# RTM_CON.net
KiCad netlist of a schematic drawn in Altium Designer
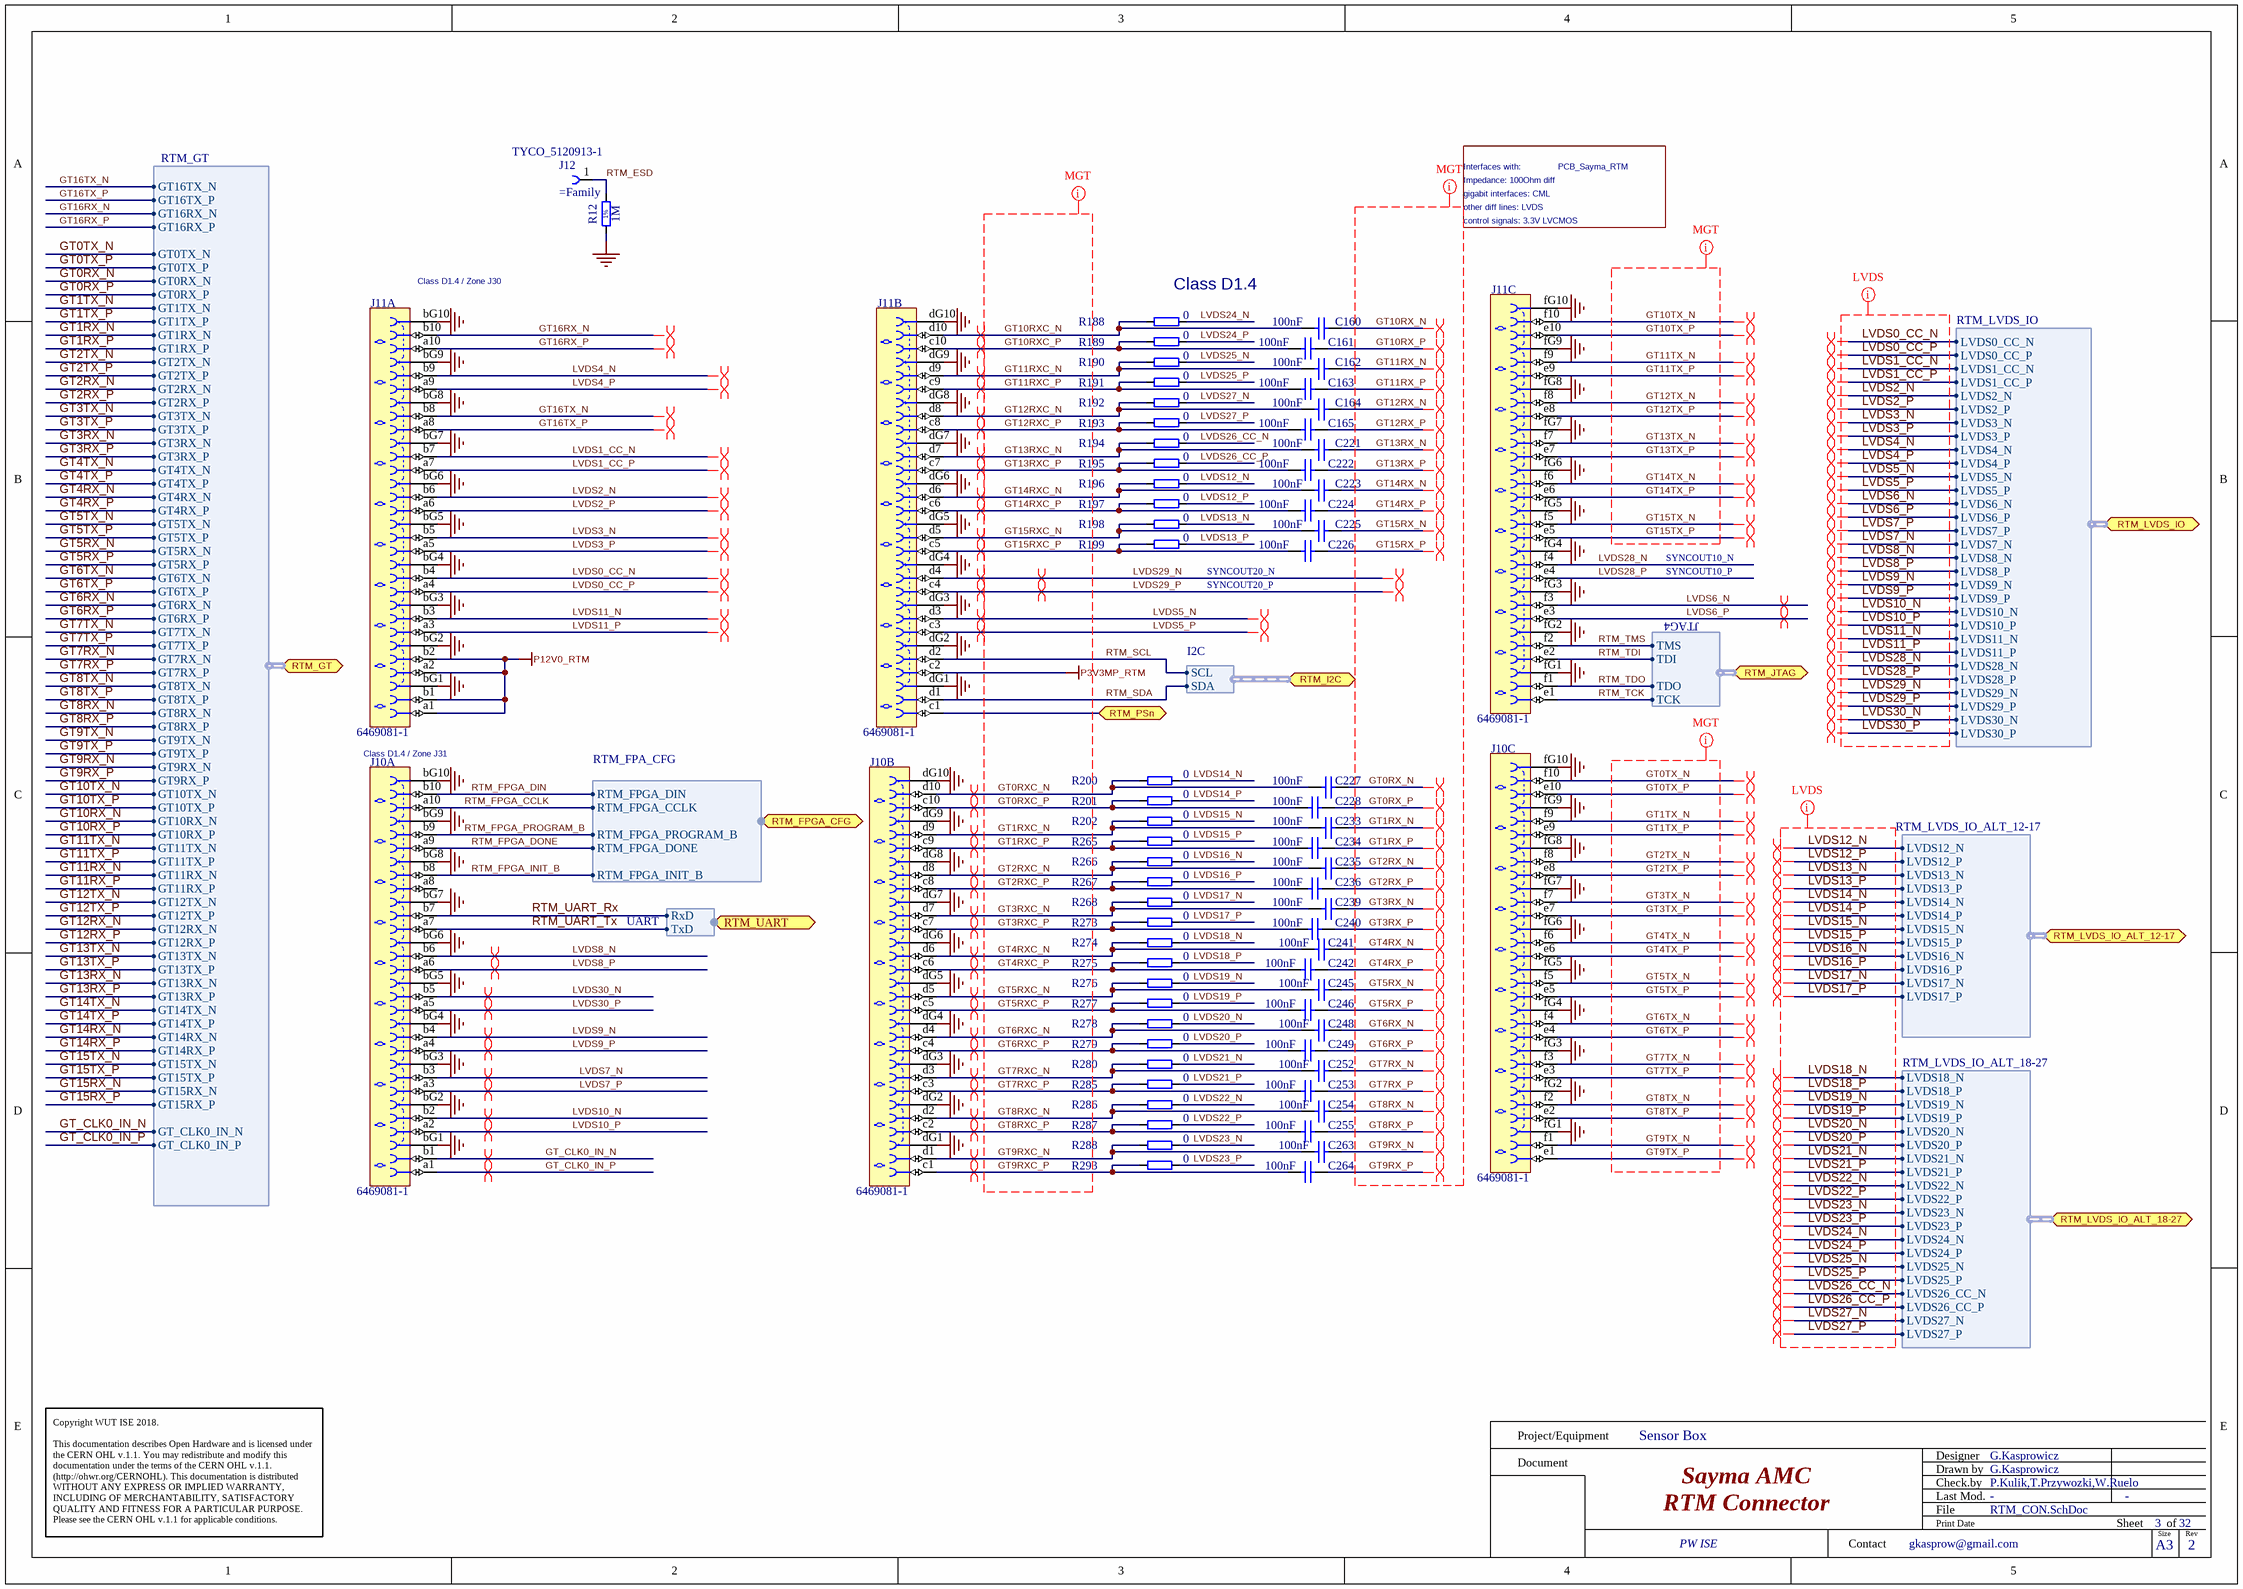
[diagram p0: RTM_CON.SchDoc]

(export (version "E")
  (design (tool "Eeschema 10.0.6"))
  (components
    (comp (ref "C160")
      (value "100nF")
      (footprint "CAPC0603X33N")
      (description "Non-polarised capacitor")
      (fields
        (field (name "MANUFACTURER PART NUMBER") "CC0201_100NF_6.3V_10%_X5R")
        (field (name "MANUFACTURER") "GENERIC")
        (field (name "AUTHOR") "CERN DEM JLC")
      )
      (libsource (lib "Capacitors") (part "Capacitor - non polarized"))
    )
    (comp (ref "C161")
      (value "100nF")
      (footprint "CAPC0603X33N")
      (description "Non-polarised capacitor")
      (fields
        (field (name "MANUFACTURER PART NUMBER") "CC0201_100NF_6.3V_10%_X5R")
        (field (name "MANUFACTURER") "GENERIC")
        (field (name "AUTHOR") "CERN DEM JLC")
      )
      (libsource (lib "Capacitors") (part "Capacitor - non polarized"))
    )
    (comp (ref "C162")
      (value "100nF")
      (footprint "CAPC0603X33N")
      (description "Non-polarised capacitor")
      (fields
        (field (name "MANUFACTURER PART NUMBER") "CC0201_100NF_6.3V_10%_X5R")
        (field (name "MANUFACTURER") "GENERIC")
        (field (name "AUTHOR") "CERN DEM JLC")
      )
      (libsource (lib "Capacitors") (part "Capacitor - non polarized"))
    )
    (comp (ref "C163")
      (value "100nF")
      (footprint "CAPC0603X33N")
      (description "Non-polarised capacitor")
      (fields
        (field (name "MANUFACTURER PART NUMBER") "CC0201_100NF_6.3V_10%_X5R")
        (field (name "MANUFACTURER") "GENERIC")
        (field (name "AUTHOR") "CERN DEM JLC")
      )
      (libsource (lib "Capacitors") (part "Capacitor - non polarized"))
    )
    (comp (ref "C164")
      (value "100nF")
      (footprint "CAPC0603X33N")
      (description "Non-polarised capacitor")
      (fields
        (field (name "MANUFACTURER PART NUMBER") "CC0201_100NF_6.3V_10%_X5R")
        (field (name "MANUFACTURER") "GENERIC")
        (field (name "AUTHOR") "CERN DEM JLC")
      )
      (libsource (lib "Capacitors") (part "Capacitor - non polarized"))
    )
    (comp (ref "C165")
      (value "100nF")
      (footprint "CAPC0603X33N")
      (description "Non-polarised capacitor")
      (fields
        (field (name "MANUFACTURER PART NUMBER") "CC0201_100NF_6.3V_10%_X5R")
        (field (name "MANUFACTURER") "GENERIC")
        (field (name "AUTHOR") "CERN DEM JLC")
      )
      (libsource (lib "Capacitors") (part "Capacitor - non polarized"))
    )
    (comp (ref "C221")
      (value "100nF")
      (footprint "CAPC0603X33N")
      (description "Non-polarised capacitor")
      (fields
        (field (name "MANUFACTURER PART NUMBER") "CC0201_100NF_6.3V_10%_X5R")
        (field (name "MANUFACTURER") "GENERIC")
        (field (name "AUTHOR") "CERN DEM JLC")
      )
      (libsource (lib "Capacitors") (part "Capacitor - non polarized"))
    )
    (comp (ref "C222")
      (value "100nF")
      (footprint "CAPC0603X33N")
      (description "Non-polarised capacitor")
      (fields
        (field (name "MANUFACTURER PART NUMBER") "CC0201_100NF_6.3V_10%_X5R")
        (field (name "MANUFACTURER") "GENERIC")
        (field (name "AUTHOR") "CERN DEM JLC")
      )
      (libsource (lib "Capacitors") (part "Capacitor - non polarized"))
    )
    (comp (ref "C223")
      (value "100nF")
      (footprint "CAPC0603X33N")
      (description "Non-polarised capacitor")
      (fields
        (field (name "MANUFACTURER PART NUMBER") "CC0201_100NF_6.3V_10%_X5R")
        (field (name "MANUFACTURER") "GENERIC")
        (field (name "AUTHOR") "CERN DEM JLC")
      )
      (libsource (lib "Capacitors") (part "Capacitor - non polarized"))
    )
    (comp (ref "C224")
      (value "100nF")
      (footprint "CAPC0603X33N")
      (description "Non-polarised capacitor")
      (fields
        (field (name "MANUFACTURER PART NUMBER") "CC0201_100NF_6.3V_10%_X5R")
        (field (name "MANUFACTURER") "GENERIC")
        (field (name "AUTHOR") "CERN DEM JLC")
      )
      (libsource (lib "Capacitors") (part "Capacitor - non polarized"))
    )
    (comp (ref "C225")
      (value "100nF")
      (footprint "CAPC0603X33N")
      (description "Non-polarised capacitor")
      (fields
        (field (name "MANUFACTURER PART NUMBER") "CC0201_100NF_6.3V_10%_X5R")
        (field (name "MANUFACTURER") "GENERIC")
        (field (name "AUTHOR") "CERN DEM JLC")
      )
      (libsource (lib "Capacitors") (part "Capacitor - non polarized"))
    )
    (comp (ref "C226")
      (value "100nF")
      (footprint "CAPC0603X33N")
      (description "Non-polarised capacitor")
      (fields
        (field (name "MANUFACTURER PART NUMBER") "CC0201_100NF_6.3V_10%_X5R")
        (field (name "MANUFACTURER") "GENERIC")
        (field (name "AUTHOR") "CERN DEM JLC")
      )
      (libsource (lib "Capacitors") (part "Capacitor - non polarized"))
    )
    (comp (ref "C227")
      (value "100nF")
      (footprint "CAPC0603X33N")
      (description "Non-polarised capacitor")
      (fields
        (field (name "MANUFACTURER PART NUMBER") "CC0201_100NF_6.3V_10%_X5R")
        (field (name "MANUFACTURER") "GENERIC")
        (field (name "AUTHOR") "CERN DEM JLC")
      )
      (libsource (lib "Capacitors") (part "Capacitor - non polarized"))
    )
    (comp (ref "C228")
      (value "100nF")
      (footprint "CAPC0603X33N")
      (description "Non-polarised capacitor")
      (fields
        (field (name "MANUFACTURER PART NUMBER") "CC0201_100NF_6.3V_10%_X5R")
        (field (name "MANUFACTURER") "GENERIC")
        (field (name "AUTHOR") "CERN DEM JLC")
      )
      (libsource (lib "Capacitors") (part "Capacitor - non polarized"))
    )
    (comp (ref "C233")
      (value "100nF")
      (footprint "CAPC0603X33N")
      (description "Non-polarised capacitor")
      (fields
        (field (name "MANUFACTURER PART NUMBER") "CC0201_100NF_6.3V_10%_X5R")
        (field (name "MANUFACTURER") "GENERIC")
        (field (name "AUTHOR") "CERN DEM JLC")
      )
      (libsource (lib "Capacitors") (part "Capacitor - non polarized"))
    )
    (comp (ref "C234")
      (value "100nF")
      (footprint "CAPC0603X33N")
      (description "Non-polarised capacitor")
      (fields
        (field (name "MANUFACTURER PART NUMBER") "CC0201_100NF_6.3V_10%_X5R")
        (field (name "MANUFACTURER") "GENERIC")
        (field (name "AUTHOR") "CERN DEM JLC")
      )
      (libsource (lib "Capacitors") (part "Capacitor - non polarized"))
    )
    (comp (ref "C235")
      (value "100nF")
      (footprint "CAPC0603X33N")
      (description "Non-polarised capacitor")
      (fields
        (field (name "MANUFACTURER PART NUMBER") "CC0201_100NF_6.3V_10%_X5R")
        (field (name "MANUFACTURER") "GENERIC")
        (field (name "AUTHOR") "CERN DEM JLC")
      )
      (libsource (lib "Capacitors") (part "Capacitor - non polarized"))
    )
    (comp (ref "C236")
      (value "100nF")
      (footprint "CAPC0603X33N")
      (description "Non-polarised capacitor")
      (fields
        (field (name "MANUFACTURER PART NUMBER") "CC0201_100NF_6.3V_10%_X5R")
        (field (name "MANUFACTURER") "GENERIC")
        (field (name "AUTHOR") "CERN DEM JLC")
      )
      (libsource (lib "Capacitors") (part "Capacitor - non polarized"))
    )
    (comp (ref "C239")
      (value "100nF")
      (footprint "CAPC0603X33N")
      (description "Non-polarised capacitor")
      (fields
        (field (name "MANUFACTURER PART NUMBER") "CC0201_100NF_6.3V_10%_X5R")
        (field (name "MANUFACTURER") "GENERIC")
        (field (name "AUTHOR") "CERN DEM JLC")
      )
      (libsource (lib "Capacitors") (part "Capacitor - non polarized"))
    )
    (comp (ref "C240")
      (value "100nF")
      (footprint "CAPC0603X33N")
      (description "Non-polarised capacitor")
      (fields
        (field (name "MANUFACTURER PART NUMBER") "CC0201_100NF_6.3V_10%_X5R")
        (field (name "MANUFACTURER") "GENERIC")
        (field (name "AUTHOR") "CERN DEM JLC")
      )
      (libsource (lib "Capacitors") (part "Capacitor - non polarized"))
    )
    (comp (ref "C241")
      (value "100nF")
      (footprint "CAPC0603X33N")
      (description "Non-polarised capacitor")
      (fields
        (field (name "MANUFACTURER PART NUMBER") "CC0201_100NF_6.3V_10%_X5R")
        (field (name "MANUFACTURER") "GENERIC")
        (field (name "AUTHOR") "CERN DEM JLC")
      )
      (libsource (lib "Capacitors") (part "Capacitor - non polarized"))
    )
    (comp (ref "C242")
      (value "100nF")
      (footprint "CAPC0603X33N")
      (description "Non-polarised capacitor")
      (fields
        (field (name "MANUFACTURER PART NUMBER") "CC0201_100NF_6.3V_10%_X5R")
        (field (name "MANUFACTURER") "GENERIC")
        (field (name "AUTHOR") "CERN DEM JLC")
      )
      (libsource (lib "Capacitors") (part "Capacitor - non polarized"))
    )
    (comp (ref "C245")
      (value "100nF")
      (footprint "CAPC0603X33N")
      (description "Non-polarised capacitor")
      (fields
        (field (name "MANUFACTURER PART NUMBER") "CC0201_100NF_6.3V_10%_X5R")
        (field (name "MANUFACTURER") "GENERIC")
        (field (name "AUTHOR") "CERN DEM JLC")
      )
      (libsource (lib "Capacitors") (part "Capacitor - non polarized"))
    )
    (comp (ref "C246")
      (value "100nF")
      (footprint "CAPC0603X33N")
      (description "Non-polarised capacitor")
      (fields
        (field (name "MANUFACTURER PART NUMBER") "CC0201_100NF_6.3V_10%_X5R")
        (field (name "MANUFACTURER") "GENERIC")
        (field (name "AUTHOR") "CERN DEM JLC")
      )
      (libsource (lib "Capacitors") (part "Capacitor - non polarized"))
    )
    (comp (ref "C248")
      (value "100nF")
      (footprint "CAPC0603X33N")
      (description "Non-polarised capacitor")
      (fields
        (field (name "MANUFACTURER PART NUMBER") "CC0201_100NF_6.3V_10%_X5R")
        (field (name "MANUFACTURER") "GENERIC")
        (field (name "AUTHOR") "CERN DEM JLC")
      )
      (libsource (lib "Capacitors") (part "Capacitor - non polarized"))
    )
    (comp (ref "C249")
      (value "100nF")
      (footprint "CAPC0603X33N")
      (description "Non-polarised capacitor")
      (fields
        (field (name "MANUFACTURER PART NUMBER") "CC0201_100NF_6.3V_10%_X5R")
        (field (name "MANUFACTURER") "GENERIC")
        (field (name "AUTHOR") "CERN DEM JLC")
      )
      (libsource (lib "Capacitors") (part "Capacitor - non polarized"))
    )
    (comp (ref "C252")
      (value "100nF")
      (footprint "CAPC0603X33N")
      (description "Non-polarised capacitor")
      (fields
        (field (name "MANUFACTURER PART NUMBER") "CC0201_100NF_6.3V_10%_X5R")
        (field (name "MANUFACTURER") "GENERIC")
        (field (name "AUTHOR") "CERN DEM JLC")
      )
      (libsource (lib "Capacitors") (part "Capacitor - non polarized"))
    )
    (comp (ref "C253")
      (value "100nF")
      (footprint "CAPC0603X33N")
      (description "Non-polarised capacitor")
      (fields
        (field (name "MANUFACTURER PART NUMBER") "CC0201_100NF_6.3V_10%_X5R")
        (field (name "MANUFACTURER") "GENERIC")
        (field (name "AUTHOR") "CERN DEM JLC")
      )
      (libsource (lib "Capacitors") (part "Capacitor - non polarized"))
    )
    (comp (ref "C254")
      (value "100nF")
      (footprint "CAPC0603X33N")
      (description "Non-polarised capacitor")
      (fields
        (field (name "MANUFACTURER PART NUMBER") "CC0201_100NF_6.3V_10%_X5R")
        (field (name "MANUFACTURER") "GENERIC")
        (field (name "AUTHOR") "CERN DEM JLC")
      )
      (libsource (lib "Capacitors") (part "Capacitor - non polarized"))
    )
    (comp (ref "C255")
      (value "100nF")
      (footprint "CAPC0603X33N")
      (description "Non-polarised capacitor")
      (fields
        (field (name "MANUFACTURER PART NUMBER") "CC0201_100NF_6.3V_10%_X5R")
        (field (name "MANUFACTURER") "GENERIC")
        (field (name "AUTHOR") "CERN DEM JLC")
      )
      (libsource (lib "Capacitors") (part "Capacitor - non polarized"))
    )
    (comp (ref "C263")
      (value "100nF")
      (footprint "CAPC0603X33N")
      (description "Non-polarised capacitor")
      (fields
        (field (name "MANUFACTURER PART NUMBER") "CC0201_100NF_6.3V_10%_X5R")
        (field (name "MANUFACTURER") "GENERIC")
        (field (name "AUTHOR") "CERN DEM JLC")
      )
      (libsource (lib "Capacitors") (part "Capacitor - non polarized"))
    )
    (comp (ref "C264")
      (value "100nF")
      (footprint "CAPC0603X33N")
      (description "Non-polarised capacitor")
      (fields
        (field (name "MANUFACTURER PART NUMBER") "CC0201_100NF_6.3V_10%_X5R")
        (field (name "MANUFACTURER") "GENERIC")
        (field (name "AUTHOR") "CERN DEM JLC")
      )
      (libsource (lib "Capacitors") (part "Capacitor - non polarized"))
    )
    (comp (ref "J10")
      (value "Advanced TCA")
      (footprint "TYCO_6469081-1")
      (description "Connector 60 ATCA Female 30 Pairs (60 Signals) + 3x10 Ground")
      (fields
        (field (name "MANUFACTURER PART NUMBER") "6469081-1")
        (field (name "MANUFACTURER") "TYCO ELECTRONICS")
        (field (name "PART NUMBER") "TYCO_6469081-1")
        (field (name "AUTHOR") "CERN DEM JLC")
      )
      (libsource (lib "Connectors") (part "Connector ATCA 60+30 Female"))
    )
    (comp (ref "J11")
      (value "Advanced TCA")
      (footprint "TYCO_6469081-1")
      (description "Connector 60 ATCA Female 30 Pairs (60 Signals) + 3x10 Ground")
      (fields
        (field (name "MANUFACTURER PART NUMBER") "6469081-1")
        (field (name "MANUFACTURER") "TYCO ELECTRONICS")
        (field (name "PART NUMBER") "TYCO_6469081-1")
        (field (name "AUTHOR") "CERN DEM JLC")
      )
      (libsource (lib "Connectors") (part "Connector ATCA 60+30 Female"))
    )
    (comp (ref "J12")
      (value "~")
      (footprint "TYCO_5120913-1")
      (description "Single Pin Female")
      (fields
        (field (name "MANUFACTURER PART NUMBER") "5120913-1")
        (field (name "MANUFACTURER") "TYCO ELECTRONICS")
        (field (name "PART NUMBER") "TYCO_5120913-1")
        (field (name "AUTHOR") "CERN DEM JLC")
      )
      (libsource (lib "Connectors") (part "Single Pin Female"))
    )
    (comp (ref "R12")
      (value "1M")
      (footprint "RESC5025X65N")
      (description "Resistor - 1%")
      (fields
        (field (name "MANUFACTURER PART NUMBER") "R2010_1M_1%_0.5W_200PPM")
        (field (name "MANUFACTURER") "GENERIC")
        (field (name "AUTHOR") "CERN DEM JLC")
      )
      (libsource (lib "Resistors") (part "Resistor - 1%"))
    )
    (comp (ref "R188")
      (value "0")
      (footprint "RESC0603X28N")
      (description "Resistor")
      (fields
        (field (name "MANUFACTURER PART NUMBER") "R0201_0R_JUMPER")
        (field (name "MANUFACTURER") "GENERIC")
        (field (name "AUTHOR") "CERN DEM JLC")
      )
      (libsource (lib "Resistors") (part "Resistor"))
    )
    (comp (ref "R189")
      (value "0")
      (footprint "RESC0603X28N")
      (description "Resistor")
      (fields
        (field (name "MANUFACTURER PART NUMBER") "R0201_0R_JUMPER")
        (field (name "MANUFACTURER") "GENERIC")
        (field (name "AUTHOR") "CERN DEM JLC")
      )
      (libsource (lib "Resistors") (part "Resistor"))
    )
    (comp (ref "R190")
      (value "0")
      (footprint "RESC0603X28N")
      (description "Resistor")
      (fields
        (field (name "MANUFACTURER PART NUMBER") "R0201_0R_JUMPER")
        (field (name "MANUFACTURER") "GENERIC")
        (field (name "AUTHOR") "CERN DEM JLC")
      )
      (libsource (lib "Resistors") (part "Resistor"))
    )
    (comp (ref "R191")
      (value "0")
      (footprint "RESC0603X28N")
      (description "Resistor")
      (fields
        (field (name "MANUFACTURER PART NUMBER") "R0201_0R_JUMPER")
        (field (name "MANUFACTURER") "GENERIC")
        (field (name "AUTHOR") "CERN DEM JLC")
      )
      (libsource (lib "Resistors") (part "Resistor"))
    )
    (comp (ref "R192")
      (value "0")
      (footprint "RESC0603X28N")
      (description "Resistor")
      (fields
        (field (name "MANUFACTURER PART NUMBER") "R0201_0R_JUMPER")
        (field (name "MANUFACTURER") "GENERIC")
        (field (name "AUTHOR") "CERN DEM JLC")
      )
      (libsource (lib "Resistors") (part "Resistor"))
    )
    (comp (ref "R193")
      (value "0")
      (footprint "RESC0603X28N")
      (description "Resistor")
      (fields
        (field (name "MANUFACTURER PART NUMBER") "R0201_0R_JUMPER")
        (field (name "MANUFACTURER") "GENERIC")
        (field (name "AUTHOR") "CERN DEM JLC")
      )
      (libsource (lib "Resistors") (part "Resistor"))
    )
    (comp (ref "R194")
      (value "0")
      (footprint "RESC0603X28N")
      (description "Resistor")
      (fields
        (field (name "MANUFACTURER PART NUMBER") "R0201_0R_JUMPER")
        (field (name "MANUFACTURER") "GENERIC")
        (field (name "AUTHOR") "CERN DEM JLC")
      )
      (libsource (lib "Resistors") (part "Resistor"))
    )
    (comp (ref "R195")
      (value "0")
      (footprint "RESC0603X28N")
      (description "Resistor")
      (fields
        (field (name "MANUFACTURER PART NUMBER") "R0201_0R_JUMPER")
        (field (name "MANUFACTURER") "GENERIC")
        (field (name "AUTHOR") "CERN DEM JLC")
      )
      (libsource (lib "Resistors") (part "Resistor"))
    )
    (comp (ref "R196")
      (value "0")
      (footprint "RESC0603X28N")
      (description "Resistor")
      (fields
        (field (name "MANUFACTURER PART NUMBER") "R0201_0R_JUMPER")
        (field (name "MANUFACTURER") "GENERIC")
        (field (name "AUTHOR") "CERN DEM JLC")
      )
      (libsource (lib "Resistors") (part "Resistor"))
    )
    (comp (ref "R197")
      (value "0")
      (footprint "RESC0603X28N")
      (description "Resistor")
      (fields
        (field (name "MANUFACTURER PART NUMBER") "R0201_0R_JUMPER")
        (field (name "MANUFACTURER") "GENERIC")
        (field (name "AUTHOR") "CERN DEM JLC")
      )
      (libsource (lib "Resistors") (part "Resistor"))
    )
    (comp (ref "R198")
      (value "0")
      (footprint "RESC0603X28N")
      (description "Resistor")
      (fields
        (field (name "MANUFACTURER PART NUMBER") "R0201_0R_JUMPER")
        (field (name "MANUFACTURER") "GENERIC")
        (field (name "AUTHOR") "CERN DEM JLC")
      )
      (libsource (lib "Resistors") (part "Resistor"))
    )
    (comp (ref "R199")
      (value "0")
      (footprint "RESC0603X28N")
      (description "Resistor")
      (fields
        (field (name "MANUFACTURER PART NUMBER") "R0201_0R_JUMPER")
        (field (name "MANUFACTURER") "GENERIC")
        (field (name "AUTHOR") "CERN DEM JLC")
      )
      (libsource (lib "Resistors") (part "Resistor"))
    )
    (comp (ref "R200")
      (value "0")
      (footprint "RESC0603X28N")
      (description "Resistor")
      (fields
        (field (name "MANUFACTURER PART NUMBER") "R0201_0R_JUMPER")
        (field (name "MANUFACTURER") "GENERIC")
        (field (name "AUTHOR") "CERN DEM JLC")
      )
      (libsource (lib "Resistors") (part "Resistor"))
    )
    (comp (ref "R201")
      (value "0")
      (footprint "RESC0603X28N")
      (description "Resistor")
      (fields
        (field (name "MANUFACTURER PART NUMBER") "R0201_0R_JUMPER")
        (field (name "MANUFACTURER") "GENERIC")
        (field (name "AUTHOR") "CERN DEM JLC")
      )
      (libsource (lib "Resistors") (part "Resistor"))
    )
    (comp (ref "R202")
      (value "0")
      (footprint "RESC0603X28N")
      (description "Resistor")
      (fields
        (field (name "MANUFACTURER PART NUMBER") "R0201_0R_JUMPER")
        (field (name "MANUFACTURER") "GENERIC")
        (field (name "AUTHOR") "CERN DEM JLC")
      )
      (libsource (lib "Resistors") (part "Resistor"))
    )
    (comp (ref "R265")
      (value "0")
      (footprint "RESC0603X28N")
      (description "Resistor")
      (fields
        (field (name "MANUFACTURER PART NUMBER") "R0201_0R_JUMPER")
        (field (name "MANUFACTURER") "GENERIC")
        (field (name "AUTHOR") "CERN DEM JLC")
      )
      (libsource (lib "Resistors") (part "Resistor"))
    )
    (comp (ref "R266")
      (value "0")
      (footprint "RESC0603X28N")
      (description "Resistor")
      (fields
        (field (name "MANUFACTURER PART NUMBER") "R0201_0R_JUMPER")
        (field (name "MANUFACTURER") "GENERIC")
        (field (name "AUTHOR") "CERN DEM JLC")
      )
      (libsource (lib "Resistors") (part "Resistor"))
    )
    (comp (ref "R267")
      (value "0")
      (footprint "RESC0603X28N")
      (description "Resistor")
      (fields
        (field (name "MANUFACTURER PART NUMBER") "R0201_0R_JUMPER")
        (field (name "MANUFACTURER") "GENERIC")
        (field (name "AUTHOR") "CERN DEM JLC")
      )
      (libsource (lib "Resistors") (part "Resistor"))
    )
    (comp (ref "R268")
      (value "0")
      (footprint "RESC0603X28N")
      (description "Resistor")
      (fields
        (field (name "MANUFACTURER PART NUMBER") "R0201_0R_JUMPER")
        (field (name "MANUFACTURER") "GENERIC")
        (field (name "AUTHOR") "CERN DEM JLC")
      )
      (libsource (lib "Resistors") (part "Resistor"))
    )
    (comp (ref "R273")
      (value "0")
      (footprint "RESC0603X28N")
      (description "Resistor")
      (fields
        (field (name "MANUFACTURER PART NUMBER") "R0201_0R_JUMPER")
        (field (name "MANUFACTURER") "GENERIC")
        (field (name "AUTHOR") "CERN DEM JLC")
      )
      (libsource (lib "Resistors") (part "Resistor"))
    )
    (comp (ref "R274")
      (value "0")
      (footprint "RESC0603X28N")
      (description "Resistor")
      (fields
        (field (name "MANUFACTURER PART NUMBER") "R0201_0R_JUMPER")
        (field (name "MANUFACTURER") "GENERIC")
        (field (name "AUTHOR") "CERN DEM JLC")
      )
      (libsource (lib "Resistors") (part "Resistor"))
    )
    (comp (ref "R275")
      (value "0")
      (footprint "RESC0603X28N")
      (description "Resistor")
      (fields
        (field (name "MANUFACTURER PART NUMBER") "R0201_0R_JUMPER")
        (field (name "MANUFACTURER") "GENERIC")
        (field (name "AUTHOR") "CERN DEM JLC")
      )
      (libsource (lib "Resistors") (part "Resistor"))
    )
    (comp (ref "R276")
      (value "0")
      (footprint "RESC0603X28N")
      (description "Resistor")
      (fields
        (field (name "MANUFACTURER PART NUMBER") "R0201_0R_JUMPER")
        (field (name "MANUFACTURER") "GENERIC")
        (field (name "AUTHOR") "CERN DEM JLC")
      )
      (libsource (lib "Resistors") (part "Resistor"))
    )
    (comp (ref "R277")
      (value "0")
      (footprint "RESC0603X28N")
      (description "Resistor")
      (fields
        (field (name "MANUFACTURER PART NUMBER") "R0201_0R_JUMPER")
        (field (name "MANUFACTURER") "GENERIC")
        (field (name "AUTHOR") "CERN DEM JLC")
      )
      (libsource (lib "Resistors") (part "Resistor"))
    )
    (comp (ref "R278")
      (value "0")
      (footprint "RESC0603X28N")
      (description "Resistor")
      (fields
        (field (name "MANUFACTURER PART NUMBER") "R0201_0R_JUMPER")
        (field (name "MANUFACTURER") "GENERIC")
        (field (name "AUTHOR") "CERN DEM JLC")
      )
      (libsource (lib "Resistors") (part "Resistor"))
    )
    (comp (ref "R279")
      (value "0")
      (footprint "RESC0603X28N")
      (description "Resistor")
      (fields
        (field (name "MANUFACTURER PART NUMBER") "R0201_0R_JUMPER")
        (field (name "MANUFACTURER") "GENERIC")
        (field (name "AUTHOR") "CERN DEM JLC")
      )
      (libsource (lib "Resistors") (part "Resistor"))
    )
    (comp (ref "R280")
      (value "0")
      (footprint "RESC0603X28N")
      (description "Resistor")
      (fields
        (field (name "MANUFACTURER PART NUMBER") "R0201_0R_JUMPER")
        (field (name "MANUFACTURER") "GENERIC")
        (field (name "AUTHOR") "CERN DEM JLC")
      )
      (libsource (lib "Resistors") (part "Resistor"))
    )
    (comp (ref "R285")
      (value "0")
      (footprint "RESC0603X28N")
      (description "Resistor")
      (fields
        (field (name "MANUFACTURER PART NUMBER") "R0201_0R_JUMPER")
        (field (name "MANUFACTURER") "GENERIC")
        (field (name "AUTHOR") "CERN DEM JLC")
      )
      (libsource (lib "Resistors") (part "Resistor"))
    )
    (comp (ref "R286")
      (value "0")
      (footprint "RESC0603X28N")
      (description "Resistor")
      (fields
        (field (name "MANUFACTURER PART NUMBER") "R0201_0R_JUMPER")
        (field (name "MANUFACTURER") "GENERIC")
        (field (name "AUTHOR") "CERN DEM JLC")
      )
      (libsource (lib "Resistors") (part "Resistor"))
    )
    (comp (ref "R287")
      (value "0")
      (footprint "RESC0603X28N")
      (description "Resistor")
      (fields
        (field (name "MANUFACTURER PART NUMBER") "R0201_0R_JUMPER")
        (field (name "MANUFACTURER") "GENERIC")
        (field (name "AUTHOR") "CERN DEM JLC")
      )
      (libsource (lib "Resistors") (part "Resistor"))
    )
    (comp (ref "R288")
      (value "0")
      (footprint "RESC0603X28N")
      (description "Resistor")
      (fields
        (field (name "MANUFACTURER PART NUMBER") "R0201_0R_JUMPER")
        (field (name "MANUFACTURER") "GENERIC")
        (field (name "AUTHOR") "CERN DEM JLC")
      )
      (libsource (lib "Resistors") (part "Resistor"))
    )
    (comp (ref "R293")
      (value "0")
      (footprint "RESC0603X28N")
      (description "Resistor")
      (fields
        (field (name "MANUFACTURER PART NUMBER") "R0201_0R_JUMPER")
        (field (name "MANUFACTURER") "GENERIC")
        (field (name "AUTHOR") "CERN DEM JLC")
      )
      (libsource (lib "Resistors") (part "Resistor"))
    )
  )
  (nets
    (net (code "9") (name "/GT0RXC_N") (class "Default")
      (node (ref "C227") (pin "1") (pinfunction "1_1") (pintype "passive"))
      (node (ref "J10") (pin "d10") (pinfunction "d10_d10") (pintype "bidirectional"))
      (node (ref "R200") (pin "1") (pinfunction "1_1") (pintype "passive"))
    )
    (net (code "10") (name "/GT0RXC_P") (class "Default")
      (node (ref "C228") (pin "1") (pinfunction "1_1") (pintype "passive"))
      (node (ref "J10") (pin "c10") (pinfunction "c10_c10") (pintype "bidirectional"))
      (node (ref "R201") (pin "1") (pinfunction "1_1") (pintype "passive"))
    )
    (net (code "11") (name "/GT0RX_N") (class "Default")
      (node (ref "C227") (pin "2") (pinfunction "2_2") (pintype "passive"))
    )
    (net (code "12") (name "/GT0RX_P") (class "Default")
      (node (ref "C228") (pin "2") (pinfunction "2_2") (pintype "passive"))
    )
    (net (code "13") (name "/GT0TX_N") (class "Default")
      (node (ref "J10") (pin "f10") (pinfunction "f10_f10") (pintype "bidirectional"))
    )
    (net (code "14") (name "/GT0TX_P") (class "Default")
      (node (ref "J10") (pin "e10") (pinfunction "e10_e10") (pintype "bidirectional"))
    )
    (net (code "15") (name "/GT1RXC_N") (class "Default")
      (node (ref "C233") (pin "1") (pinfunction "1_1") (pintype "passive"))
      (node (ref "J10") (pin "d9") (pinfunction "d9_d9") (pintype "bidirectional"))
      (node (ref "R202") (pin "1") (pinfunction "1_1") (pintype "passive"))
    )
    (net (code "16") (name "/GT1RXC_P") (class "Default")
      (node (ref "C234") (pin "1") (pinfunction "1_1") (pintype "passive"))
      (node (ref "J10") (pin "c9") (pinfunction "c9_c9") (pintype "bidirectional"))
      (node (ref "R265") (pin "1") (pinfunction "1_1") (pintype "passive"))
    )
    (net (code "17") (name "/GT1RX_N") (class "Default")
      (node (ref "C233") (pin "2") (pinfunction "2_2") (pintype "passive"))
    )
    (net (code "18") (name "/GT1RX_P") (class "Default")
      (node (ref "C234") (pin "2") (pinfunction "2_2") (pintype "passive"))
    )
    (net (code "19") (name "/GT1TX_N") (class "Default")
      (node (ref "J10") (pin "f9") (pinfunction "f9_f9") (pintype "bidirectional"))
    )
    (net (code "20") (name "/GT1TX_P") (class "Default")
      (node (ref "J10") (pin "e9") (pinfunction "e9_e9") (pintype "bidirectional"))
    )
    (net (code "21") (name "/GT2RXC_N") (class "Default")
      (node (ref "C235") (pin "1") (pinfunction "1_1") (pintype "passive"))
      (node (ref "J10") (pin "d8") (pinfunction "d8_d8") (pintype "bidirectional"))
      (node (ref "R266") (pin "1") (pinfunction "1_1") (pintype "passive"))
    )
    (net (code "22") (name "/GT2RXC_P") (class "Default")
      (node (ref "C236") (pin "1") (pinfunction "1_1") (pintype "passive"))
      (node (ref "J10") (pin "c8") (pinfunction "c8_c8") (pintype "bidirectional"))
      (node (ref "R267") (pin "1") (pinfunction "1_1") (pintype "passive"))
    )
    (net (code "23") (name "/GT2RX_N") (class "Default")
      (node (ref "C235") (pin "2") (pinfunction "2_2") (pintype "passive"))
    )
    (net (code "24") (name "/GT2RX_P") (class "Default")
      (node (ref "C236") (pin "2") (pinfunction "2_2") (pintype "passive"))
    )
    (net (code "25") (name "/GT2TX_N") (class "Default")
      (node (ref "J10") (pin "f8") (pinfunction "f8_f8") (pintype "bidirectional"))
    )
    (net (code "26") (name "/GT2TX_P") (class "Default")
      (node (ref "J10") (pin "e8") (pinfunction "e8_e8") (pintype "bidirectional"))
    )
    (net (code "27") (name "/GT3RXC_N") (class "Default")
      (node (ref "C239") (pin "1") (pinfunction "1_1") (pintype "passive"))
      (node (ref "J10") (pin "d7") (pinfunction "d7_d7") (pintype "bidirectional"))
      (node (ref "R268") (pin "1") (pinfunction "1_1") (pintype "passive"))
    )
    (net (code "28") (name "/GT3RXC_P") (class "Default")
      (node (ref "C240") (pin "1") (pinfunction "1_1") (pintype "passive"))
      (node (ref "J10") (pin "c7") (pinfunction "c7_c7") (pintype "bidirectional"))
      (node (ref "R273") (pin "1") (pinfunction "1_1") (pintype "passive"))
    )
    (net (code "29") (name "/GT3RX_N") (class "Default")
      (node (ref "C239") (pin "2") (pinfunction "2_2") (pintype "passive"))
    )
    (net (code "30") (name "/GT3RX_P") (class "Default")
      (node (ref "C240") (pin "2") (pinfunction "2_2") (pintype "passive"))
    )
    (net (code "31") (name "/GT3TX_N") (class "Default")
      (node (ref "J10") (pin "f7") (pinfunction "f7_f7") (pintype "bidirectional"))
    )
    (net (code "32") (name "/GT3TX_P") (class "Default")
      (node (ref "J10") (pin "e7") (pinfunction "e7_e7") (pintype "bidirectional"))
    )
    (net (code "33") (name "/GT4RXC_N") (class "Default")
      (node (ref "C241") (pin "1") (pinfunction "1_1") (pintype "passive"))
      (node (ref "J10") (pin "d6") (pinfunction "d6_d6") (pintype "bidirectional"))
      (node (ref "R274") (pin "1") (pinfunction "1_1") (pintype "passive"))
    )
    (net (code "34") (name "/GT4RXC_P") (class "Default")
      (node (ref "C242") (pin "1") (pinfunction "1_1") (pintype "passive"))
      (node (ref "J10") (pin "c6") (pinfunction "c6_c6") (pintype "bidirectional"))
      (node (ref "R275") (pin "1") (pinfunction "1_1") (pintype "passive"))
    )
    (net (code "35") (name "/GT4RX_N") (class "Default")
      (node (ref "C241") (pin "2") (pinfunction "2_2") (pintype "passive"))
    )
    (net (code "36") (name "/GT4RX_P") (class "Default")
      (node (ref "C242") (pin "2") (pinfunction "2_2") (pintype "passive"))
    )
    (net (code "37") (name "/GT4TX_N") (class "Default")
      (node (ref "J10") (pin "f6") (pinfunction "f6_f6") (pintype "bidirectional"))
    )
    (net (code "38") (name "/GT4TX_P") (class "Default")
      (node (ref "J10") (pin "e6") (pinfunction "e6_e6") (pintype "bidirectional"))
    )
    (net (code "39") (name "/GT5RXC_N") (class "Default")
      (node (ref "C245") (pin "1") (pinfunction "1_1") (pintype "passive"))
      (node (ref "J10") (pin "d5") (pinfunction "d5_d5") (pintype "bidirectional"))
      (node (ref "R276") (pin "1") (pinfunction "1_1") (pintype "passive"))
    )
    (net (code "40") (name "/GT5RXC_P") (class "Default")
      (node (ref "C246") (pin "1") (pinfunction "1_1") (pintype "passive"))
      (node (ref "J10") (pin "c5") (pinfunction "c5_c5") (pintype "bidirectional"))
      (node (ref "R277") (pin "1") (pinfunction "1_1") (pintype "passive"))
    )
    (net (code "41") (name "/GT5RX_N") (class "Default")
      (node (ref "C245") (pin "2") (pinfunction "2_2") (pintype "passive"))
    )
    (net (code "42") (name "/GT5RX_P") (class "Default")
      (node (ref "C246") (pin "2") (pinfunction "2_2") (pintype "passive"))
    )
    (net (code "43") (name "/GT5TX_N") (class "Default")
      (node (ref "J10") (pin "f5") (pinfunction "f5_f5") (pintype "bidirectional"))
    )
    (net (code "44") (name "/GT5TX_P") (class "Default")
      (node (ref "J10") (pin "e5") (pinfunction "e5_e5") (pintype "bidirectional"))
    )
    (net (code "45") (name "/GT6RXC_N") (class "Default")
      (node (ref "C248") (pin "1") (pinfunction "1_1") (pintype "passive"))
      (node (ref "J10") (pin "d4") (pinfunction "d4_d4") (pintype "bidirectional"))
      (node (ref "R278") (pin "1") (pinfunction "1_1") (pintype "passive"))
    )
    (net (code "46") (name "/GT6RXC_P") (class "Default")
      (node (ref "C249") (pin "1") (pinfunction "1_1") (pintype "passive"))
      (node (ref "J10") (pin "c4") (pinfunction "c4_c4") (pintype "bidirectional"))
      (node (ref "R279") (pin "1") (pinfunction "1_1") (pintype "passive"))
    )
    (net (code "47") (name "/GT6RX_N") (class "Default")
      (node (ref "C248") (pin "2") (pinfunction "2_2") (pintype "passive"))
    )
    (net (code "48") (name "/GT6RX_P") (class "Default")
      (node (ref "C249") (pin "2") (pinfunction "2_2") (pintype "passive"))
    )
    (net (code "49") (name "/GT6TX_N") (class "Default")
      (node (ref "J10") (pin "f4") (pinfunction "f4_f4") (pintype "bidirectional"))
    )
    (net (code "50") (name "/GT6TX_P") (class "Default")
      (node (ref "J10") (pin "e4") (pinfunction "e4_e4") (pintype "bidirectional"))
    )
    (net (code "51") (name "/GT7RXC_N") (class "Default")
      (node (ref "C252") (pin "1") (pinfunction "1_1") (pintype "passive"))
      (node (ref "J10") (pin "d3") (pinfunction "d3_d3") (pintype "bidirectional"))
      (node (ref "R280") (pin "1") (pinfunction "1_1") (pintype "passive"))
    )
    (net (code "52") (name "/GT7RXC_P") (class "Default")
      (node (ref "C253") (pin "1") (pinfunction "1_1") (pintype "passive"))
      (node (ref "J10") (pin "c3") (pinfunction "c3_c3") (pintype "bidirectional"))
      (node (ref "R285") (pin "1") (pinfunction "1_1") (pintype "passive"))
    )
    (net (code "53") (name "/GT7RX_N") (class "Default")
      (node (ref "C252") (pin "2") (pinfunction "2_2") (pintype "passive"))
    )
    (net (code "54") (name "/GT7RX_P") (class "Default")
      (node (ref "C253") (pin "2") (pinfunction "2_2") (pintype "passive"))
    )
    (net (code "55") (name "/GT7TX_N") (class "Default")
      (node (ref "J10") (pin "f3") (pinfunction "f3_f3") (pintype "bidirectional"))
    )
    (net (code "56") (name "/GT7TX_P") (class "Default")
      (node (ref "J10") (pin "e3") (pinfunction "e3_e3") (pintype "bidirectional"))
    )
    (net (code "57") (name "/GT8RXC_N") (class "Default")
      (node (ref "C254") (pin "1") (pinfunction "1_1") (pintype "passive"))
      (node (ref "J10") (pin "d2") (pinfunction "d2_d2") (pintype "bidirectional"))
      (node (ref "R286") (pin "1") (pinfunction "1_1") (pintype "passive"))
    )
    (net (code "58") (name "/GT8RXC_P") (class "Default")
      (node (ref "C255") (pin "1") (pinfunction "1_1") (pintype "passive"))
      (node (ref "J10") (pin "c2") (pinfunction "c2_c2") (pintype "bidirectional"))
      (node (ref "R287") (pin "1") (pinfunction "1_1") (pintype "passive"))
    )
    (net (code "59") (name "/GT8RX_N") (class "Default")
      (node (ref "C254") (pin "2") (pinfunction "2_2") (pintype "passive"))
    )
    (net (code "60") (name "/GT8RX_P") (class "Default")
      (node (ref "C255") (pin "2") (pinfunction "2_2") (pintype "passive"))
    )
    (net (code "61") (name "/GT8TX_N") (class "Default")
      (node (ref "J10") (pin "f2") (pinfunction "f2_f2") (pintype "bidirectional"))
    )
    (net (code "62") (name "/GT8TX_P") (class "Default")
      (node (ref "J10") (pin "e2") (pinfunction "e2_e2") (pintype "bidirectional"))
    )
    (net (code "63") (name "/GT9RXC_N") (class "Default")
      (node (ref "C263") (pin "1") (pinfunction "1_1") (pintype "passive"))
      (node (ref "J10") (pin "d1") (pinfunction "d1_d1") (pintype "bidirectional"))
      (node (ref "R288") (pin "1") (pinfunction "1_1") (pintype "passive"))
    )
    (net (code "64") (name "/GT9RXC_P") (class "Default")
      (node (ref "C264") (pin "1") (pinfunction "1_1") (pintype "passive"))
      (node (ref "J10") (pin "c1") (pinfunction "c1_c1") (pintype "bidirectional"))
      (node (ref "R293") (pin "1") (pinfunction "1_1") (pintype "passive"))
    )
    (net (code "65") (name "/GT9RX_N") (class "Default")
      (node (ref "C263") (pin "2") (pinfunction "2_2") (pintype "passive"))
    )
    (net (code "66") (name "/GT9RX_P") (class "Default")
      (node (ref "C264") (pin "2") (pinfunction "2_2") (pintype "passive"))
    )
    (net (code "67") (name "/GT9TX_N") (class "Default")
      (node (ref "J10") (pin "f1") (pinfunction "f1_f1") (pintype "bidirectional"))
    )
    (net (code "68") (name "/GT9TX_P") (class "Default")
      (node (ref "J10") (pin "e1") (pinfunction "e1_e1") (pintype "bidirectional"))
    )
    (net (code "69") (name "/GT10RXC_N") (class "Default")
      (node (ref "C160") (pin "1") (pinfunction "1_1") (pintype "passive"))
      (node (ref "J11") (pin "d10") (pinfunction "d10_d10") (pintype "bidirectional"))
      (node (ref "R188") (pin "1") (pinfunction "1_1") (pintype "passive"))
    )
    (net (code "70") (name "/GT10RXC_P") (class "Default")
      (node (ref "C161") (pin "1") (pinfunction "1_1") (pintype "passive"))
      (node (ref "J11") (pin "c10") (pinfunction "c10_c10") (pintype "bidirectional"))
      (node (ref "R189") (pin "1") (pinfunction "1_1") (pintype "passive"))
    )
    (net (code "71") (name "/GT10RX_N") (class "Default")
      (node (ref "C160") (pin "2") (pinfunction "2_2") (pintype "passive"))
    )
    (net (code "72") (name "/GT10RX_P") (class "Default")
      (node (ref "C161") (pin "2") (pinfunction "2_2") (pintype "passive"))
    )
    (net (code "73") (name "/GT10TX_N") (class "Default")
      (node (ref "J11") (pin "f10") (pinfunction "f10_f10") (pintype "bidirectional"))
    )
    (net (code "74") (name "/GT10TX_P") (class "Default")
      (node (ref "J11") (pin "e10") (pinfunction "e10_e10") (pintype "bidirectional"))
    )
    (net (code "75") (name "/GT11RXC_N") (class "Default")
      (node (ref "C162") (pin "1") (pinfunction "1_1") (pintype "passive"))
      (node (ref "J11") (pin "d9") (pinfunction "d9_d9") (pintype "bidirectional"))
      (node (ref "R190") (pin "1") (pinfunction "1_1") (pintype "passive"))
    )
    (net (code "76") (name "/GT11RXC_P") (class "Default")
      (node (ref "C163") (pin "1") (pinfunction "1_1") (pintype "passive"))
      (node (ref "J11") (pin "c9") (pinfunction "c9_c9") (pintype "bidirectional"))
      (node (ref "R191") (pin "1") (pinfunction "1_1") (pintype "passive"))
    )
    (net (code "77") (name "/GT11RX_N") (class "Default")
      (node (ref "C162") (pin "2") (pinfunction "2_2") (pintype "passive"))
    )
    (net (code "78") (name "/GT11RX_P") (class "Default")
      (node (ref "C163") (pin "2") (pinfunction "2_2") (pintype "passive"))
    )
    (net (code "79") (name "/GT11TX_N") (class "Default")
      (node (ref "J11") (pin "f9") (pinfunction "f9_f9") (pintype "bidirectional"))
    )
    (net (code "80") (name "/GT11TX_P") (class "Default")
      (node (ref "J11") (pin "e9") (pinfunction "e9_e9") (pintype "bidirectional"))
    )
    (net (code "81") (name "/GT12RXC_N") (class "Default")
      (node (ref "C164") (pin "1") (pinfunction "1_1") (pintype "passive"))
      (node (ref "J11") (pin "d8") (pinfunction "d8_d8") (pintype "bidirectional"))
      (node (ref "R192") (pin "1") (pinfunction "1_1") (pintype "passive"))
    )
    (net (code "82") (name "/GT12RXC_P") (class "Default")
      (node (ref "C165") (pin "1") (pinfunction "1_1") (pintype "passive"))
      (node (ref "J11") (pin "c8") (pinfunction "c8_c8") (pintype "bidirectional"))
      (node (ref "R193") (pin "1") (pinfunction "1_1") (pintype "passive"))
    )
    (net (code "83") (name "/GT12RX_N") (class "Default")
      (node (ref "C164") (pin "2") (pinfunction "2_2") (pintype "passive"))
    )
    (net (code "84") (name "/GT12RX_P") (class "Default")
      (node (ref "C165") (pin "2") (pinfunction "2_2") (pintype "passive"))
    )
    (net (code "85") (name "/GT12TX_N") (class "Default")
      (node (ref "J11") (pin "f8") (pinfunction "f8_f8") (pintype "bidirectional"))
    )
    (net (code "86") (name "/GT12TX_P") (class "Default")
      (node (ref "J11") (pin "e8") (pinfunction "e8_e8") (pintype "bidirectional"))
    )
    (net (code "87") (name "/GT13RXC_N") (class "Default")
      (node (ref "C221") (pin "1") (pinfunction "1_1") (pintype "passive"))
      (node (ref "J11") (pin "d7") (pinfunction "d7_d7") (pintype "bidirectional"))
      (node (ref "R194") (pin "1") (pinfunction "1_1") (pintype "passive"))
    )
    (net (code "88") (name "/GT13RXC_P") (class "Default")
      (node (ref "C222") (pin "1") (pinfunction "1_1") (pintype "passive"))
      (node (ref "J11") (pin "c7") (pinfunction "c7_c7") (pintype "bidirectional"))
      (node (ref "R195") (pin "1") (pinfunction "1_1") (pintype "passive"))
    )
    (net (code "89") (name "/GT13RX_N") (class "Default")
      (node (ref "C221") (pin "2") (pinfunction "2_2") (pintype "passive"))
    )
    (net (code "90") (name "/GT13RX_P") (class "Default")
      (node (ref "C222") (pin "2") (pinfunction "2_2") (pintype "passive"))
    )
    (net (code "91") (name "/GT13TX_N") (class "Default")
      (node (ref "J11") (pin "f7") (pinfunction "f7_f7") (pintype "bidirectional"))
    )
    (net (code "92") (name "/GT13TX_P") (class "Default")
      (node (ref "J11") (pin "e7") (pinfunction "e7_e7") (pintype "bidirectional"))
    )
    (net (code "93") (name "/GT14RXC_N") (class "Default")
      (node (ref "C223") (pin "1") (pinfunction "1_1") (pintype "passive"))
      (node (ref "J11") (pin "d6") (pinfunction "d6_d6") (pintype "bidirectional"))
      (node (ref "R196") (pin "1") (pinfunction "1_1") (pintype "passive"))
    )
    (net (code "94") (name "/GT14RXC_P") (class "Default")
      (node (ref "C224") (pin "1") (pinfunction "1_1") (pintype "passive"))
      (node (ref "J11") (pin "c6") (pinfunction "c6_c6") (pintype "bidirectional"))
      (node (ref "R197") (pin "1") (pinfunction "1_1") (pintype "passive"))
    )
    (net (code "95") (name "/GT14RX_N") (class "Default")
      (node (ref "C223") (pin "2") (pinfunction "2_2") (pintype "passive"))
    )
    (net (code "96") (name "/GT14RX_P") (class "Default")
      (node (ref "C224") (pin "2") (pinfunction "2_2") (pintype "passive"))
    )
    (net (code "97") (name "/GT14TX_N") (class "Default")
      (node (ref "J11") (pin "f6") (pinfunction "f6_f6") (pintype "bidirectional"))
    )
    (net (code "98") (name "/GT14TX_P") (class "Default")
      (node (ref "J11") (pin "e6") (pinfunction "e6_e6") (pintype "bidirectional"))
    )
    (net (code "99") (name "/GT15RXC_N") (class "Default")
      (node (ref "C225") (pin "1") (pinfunction "1_1") (pintype "passive"))
      (node (ref "J11") (pin "d5") (pinfunction "d5_d5") (pintype "bidirectional"))
      (node (ref "R198") (pin "1") (pinfunction "1_1") (pintype "passive"))
    )
    (net (code "100") (name "/GT15RXC_P") (class "Default")
      (node (ref "C226") (pin "1") (pinfunction "1_1") (pintype "passive"))
      (node (ref "J11") (pin "c5") (pinfunction "c5_c5") (pintype "bidirectional"))
      (node (ref "R199") (pin "1") (pinfunction "1_1") (pintype "passive"))
    )
    (net (code "101") (name "/GT15RX_N") (class "Default")
      (node (ref "C225") (pin "2") (pinfunction "2_2") (pintype "passive"))
    )
    (net (code "102") (name "/GT15RX_P") (class "Default")
      (node (ref "C226") (pin "2") (pinfunction "2_2") (pintype "passive"))
    )
    (net (code "103") (name "/GT15TX_N") (class "Default")
      (node (ref "J11") (pin "f5") (pinfunction "f5_f5") (pintype "bidirectional"))
    )
    (net (code "104") (name "/GT15TX_P") (class "Default")
      (node (ref "J11") (pin "e5") (pinfunction "e5_e5") (pintype "bidirectional"))
    )
    (net (code "105") (name "/GT16RX_N") (class "Default")
      (node (ref "J11") (pin "b10") (pinfunction "b10_b10") (pintype "bidirectional"))
    )
    (net (code "106") (name "/GT16RX_P") (class "Default")
      (node (ref "J11") (pin "a10") (pinfunction "a10_a10") (pintype "bidirectional"))
    )
    (net (code "107") (name "/GT16TX_N") (class "Default")
      (node (ref "J11") (pin "b8") (pinfunction "b8_b8") (pintype "bidirectional"))
    )
    (net (code "108") (name "/GT16TX_P") (class "Default")
      (node (ref "J11") (pin "a8") (pinfunction "a8_a8") (pintype "bidirectional"))
    )
    (net (code "109") (name "/GT_CLK0_IN_N") (class "Default")
      (node (ref "J10") (pin "b1") (pinfunction "b1_b1") (pintype "bidirectional"))
    )
    (net (code "110") (name "/GT_CLK0_IN_P") (class "Default")
      (node (ref "J10") (pin "a1") (pinfunction "a1_a1") (pintype "bidirectional"))
    )
    (net (code "111") (name "/LVDS0_CC_N") (class "Default")
      (node (ref "J11") (pin "b4") (pinfunction "b4_b4") (pintype "bidirectional"))
    )
    (net (code "112") (name "/LVDS0_CC_P") (class "Default")
      (node (ref "J11") (pin "a4") (pinfunction "a4_a4") (pintype "bidirectional"))
    )
    (net (code "113") (name "/LVDS1_CC_N") (class "Default")
      (node (ref "J11") (pin "b7") (pinfunction "b7_b7") (pintype "bidirectional"))
    )
    (net (code "114") (name "/LVDS1_CC_P") (class "Default")
      (node (ref "J11") (pin "a7") (pinfunction "a7_a7") (pintype "bidirectional"))
    )
    (net (code "115") (name "/LVDS2_N") (class "Default")
      (node (ref "J11") (pin "b6") (pinfunction "b6_b6") (pintype "bidirectional"))
    )
    (net (code "116") (name "/LVDS2_P") (class "Default")
      (node (ref "J11") (pin "a6") (pinfunction "a6_a6") (pintype "bidirectional"))
    )
    (net (code "117") (name "/LVDS3_N") (class "Default")
      (node (ref "J11") (pin "b5") (pinfunction "b5_b5") (pintype "bidirectional"))
    )
    (net (code "118") (name "/LVDS3_P") (class "Default")
      (node (ref "J11") (pin "a5") (pinfunction "a5_a5") (pintype "bidirectional"))
    )
    (net (code "119") (name "/LVDS4_N") (class "Default")
      (node (ref "J11") (pin "b9") (pinfunction "b9_b9") (pintype "bidirectional"))
    )
    (net (code "120") (name "/LVDS4_P") (class "Default")
      (node (ref "J11") (pin "a9") (pinfunction "a9_a9") (pintype "bidirectional"))
    )
    (net (code "121") (name "/LVDS5_N") (class "Default")
      (node (ref "J11") (pin "d3") (pinfunction "d3_d3") (pintype "bidirectional"))
    )
    (net (code "122") (name "/LVDS5_P") (class "Default")
      (node (ref "J11") (pin "c3") (pinfunction "c3_c3") (pintype "bidirectional"))
    )
    (net (code "123") (name "/LVDS6_N") (class "Default")
      (node (ref "J11") (pin "f3") (pinfunction "f3_f3") (pintype "bidirectional"))
    )
    (net (code "124") (name "/LVDS6_P") (class "Default")
      (node (ref "J11") (pin "e3") (pinfunction "e3_e3") (pintype "bidirectional"))
    )
    (net (code "125") (name "/LVDS7_N") (class "Default")
      (node (ref "J10") (pin "b3") (pinfunction "b3_b3") (pintype "bidirectional"))
    )
    (net (code "126") (name "/LVDS7_P") (class "Default")
      (node (ref "J10") (pin "a3") (pinfunction "a3_a3") (pintype "bidirectional"))
    )
    (net (code "127") (name "/LVDS8_N") (class "Default")
      (node (ref "J10") (pin "b6") (pinfunction "b6_b6") (pintype "bidirectional"))
    )
    (net (code "128") (name "/LVDS8_P") (class "Default")
      (node (ref "J10") (pin "a6") (pinfunction "a6_a6") (pintype "bidirectional"))
    )
    (net (code "129") (name "/LVDS9_N") (class "Default")
      (node (ref "J10") (pin "b4") (pinfunction "b4_b4") (pintype "bidirectional"))
    )
    (net (code "130") (name "/LVDS9_P") (class "Default")
      (node (ref "J10") (pin "a4") (pinfunction "a4_a4") (pintype "bidirectional"))
    )
    (net (code "131") (name "/LVDS10_N") (class "Default")
      (node (ref "J10") (pin "b2") (pinfunction "b2_b2") (pintype "bidirectional"))
    )
    (net (code "132") (name "/LVDS10_P") (class "Default")
      (node (ref "J10") (pin "a2") (pinfunction "a2_a2") (pintype "bidirectional"))
    )
    (net (code "133") (name "/LVDS11_N") (class "Default")
      (node (ref "J11") (pin "b3") (pinfunction "b3_b3") (pintype "bidirectional"))
    )
    (net (code "134") (name "/LVDS11_P") (class "Default")
      (node (ref "J11") (pin "a3") (pinfunction "a3_a3") (pintype "bidirectional"))
    )
    (net (code "135") (name "/LVDS12_N") (class "Default")
      (node (ref "R196") (pin "2") (pinfunction "2_2") (pintype "passive"))
    )
    (net (code "136") (name "/LVDS12_P") (class "Default")
      (node (ref "R197") (pin "2") (pinfunction "2_2") (pintype "passive"))
    )
    (net (code "137") (name "/LVDS13_N") (class "Default")
      (node (ref "R198") (pin "2") (pinfunction "2_2") (pintype "passive"))
    )
    (net (code "138") (name "/LVDS13_P") (class "Default")
      (node (ref "R199") (pin "2") (pinfunction "2_2") (pintype "passive"))
    )
    (net (code "139") (name "/LVDS14_N") (class "Default")
      (node (ref "R200") (pin "2") (pinfunction "2_2") (pintype "passive"))
    )
    (net (code "140") (name "/LVDS14_P") (class "Default")
      (node (ref "R201") (pin "2") (pinfunction "2_2") (pintype "passive"))
    )
    (net (code "141") (name "/LVDS15_N") (class "Default")
      (node (ref "R202") (pin "2") (pinfunction "2_2") (pintype "passive"))
    )
    (net (code "142") (name "/LVDS15_P") (class "Default")
      (node (ref "R265") (pin "2") (pinfunction "2_2") (pintype "passive"))
    )
    (net (code "143") (name "/LVDS16_N") (class "Default")
      (node (ref "R266") (pin "2") (pinfunction "2_2") (pintype "passive"))
    )
    (net (code "144") (name "/LVDS16_P") (class "Default")
      (node (ref "R267") (pin "2") (pinfunction "2_2") (pintype "passive"))
    )
    (net (code "145") (name "/LVDS17_N") (class "Default")
      (node (ref "R268") (pin "2") (pinfunction "2_2") (pintype "passive"))
    )
    (net (code "146") (name "/LVDS17_P") (class "Default")
      (node (ref "R273") (pin "2") (pinfunction "2_2") (pintype "passive"))
    )
    (net (code "147") (name "/LVDS18_N") (class "Default")
      (node (ref "R274") (pin "2") (pinfunction "2_2") (pintype "passive"))
    )
    (net (code "148") (name "/LVDS18_P") (class "Default")
      (node (ref "R275") (pin "2") (pinfunction "2_2") (pintype "passive"))
    )
    (net (code "149") (name "/LVDS19_N") (class "Default")
      (node (ref "R276") (pin "2") (pinfunction "2_2") (pintype "passive"))
    )
    (net (code "150") (name "/LVDS19_P") (class "Default")
      (node (ref "R277") (pin "2") (pinfunction "2_2") (pintype "passive"))
    )
    (net (code "151") (name "/LVDS20_N") (class "Default")
      (node (ref "R278") (pin "2") (pinfunction "2_2") (pintype "passive"))
    )
    (net (code "152") (name "/LVDS20_P") (class "Default")
      (node (ref "R279") (pin "2") (pinfunction "2_2") (pintype "passive"))
    )
    (net (code "153") (name "/LVDS21_N") (class "Default")
      (node (ref "R280") (pin "2") (pinfunction "2_2") (pintype "passive"))
    )
    (net (code "154") (name "/LVDS21_P") (class "Default")
      (node (ref "R285") (pin "2") (pinfunction "2_2") (pintype "passive"))
    )
    (net (code "155") (name "/LVDS22_N") (class "Default")
      (node (ref "R286") (pin "2") (pinfunction "2_2") (pintype "passive"))
    )
    (net (code "156") (name "/LVDS22_P") (class "Default")
      (node (ref "R287") (pin "2") (pinfunction "2_2") (pintype "passive"))
    )
    (net (code "157") (name "/LVDS23_N") (class "Default")
      (node (ref "R288") (pin "2") (pinfunction "2_2") (pintype "passive"))
    )
    (net (code "158") (name "/LVDS23_P") (class "Default")
      (node (ref "R293") (pin "2") (pinfunction "2_2") (pintype "passive"))
    )
    (net (code "159") (name "/LVDS24_N") (class "Default")
      (node (ref "R188") (pin "2") (pinfunction "2_2") (pintype "passive"))
    )
    (net (code "160") (name "/LVDS24_P") (class "Default")
      (node (ref "R189") (pin "2") (pinfunction "2_2") (pintype "passive"))
    )
    (net (code "161") (name "/LVDS25_N") (class "Default")
      (node (ref "R190") (pin "2") (pinfunction "2_2") (pintype "passive"))
    )
    (net (code "162") (name "/LVDS25_P") (class "Default")
      (node (ref "R191") (pin "2") (pinfunction "2_2") (pintype "passive"))
    )
    (net (code "163") (name "/LVDS26_CC_N") (class "Default")
      (node (ref "R194") (pin "2") (pinfunction "2_2") (pintype "passive"))
    )
    (net (code "164") (name "/LVDS26_CC_P") (class "Default")
      (node (ref "R195") (pin "2") (pinfunction "2_2") (pintype "passive"))
    )
    (net (code "165") (name "/LVDS27_N") (class "Default")
      (node (ref "R192") (pin "2") (pinfunction "2_2") (pintype "passive"))
    )
    (net (code "166") (name "/LVDS27_P") (class "Default")
      (node (ref "R193") (pin "2") (pinfunction "2_2") (pintype "passive"))
    )
    (net (code "167") (name "/LVDS28_N") (class "Default")
      (node (ref "J11") (pin "f4") (pinfunction "f4_f4") (pintype "bidirectional"))
    )
    (net (code "168") (name "/LVDS28_P") (class "Default")
      (node (ref "J11") (pin "e4") (pinfunction "e4_e4") (pintype "bidirectional"))
    )
    (net (code "169") (name "/LVDS29_N") (class "Default")
      (node (ref "J11") (pin "d4") (pinfunction "d4_d4") (pintype "bidirectional"))
    )
    (net (code "170") (name "/LVDS29_P") (class "Default")
      (node (ref "J11") (pin "c4") (pinfunction "c4_c4") (pintype "bidirectional"))
    )
    (net (code "171") (name "/LVDS30_N") (class "Default")
      (node (ref "J10") (pin "b5") (pinfunction "b5_b5") (pintype "bidirectional"))
    )
    (net (code "172") (name "/LVDS30_P") (class "Default")
      (node (ref "J10") (pin "a5") (pinfunction "a5_a5") (pintype "bidirectional"))
    )
    (net (code "173") (name "/RTM_ESD") (class "Default")
      (node (ref "J12") (pin "1") (pinfunction "1_1") (pintype "bidirectional"))
      (node (ref "R12") (pin "2") (pinfunction "2_2") (pintype "passive"))
    )
    (net (code "174") (name "/RTM_FPGA_CCLK") (class "Default")
      (node (ref "J10") (pin "a10") (pinfunction "a10_a10") (pintype "bidirectional"))
    )
    (net (code "175") (name "/RTM_FPGA_DIN") (class "Default")
      (node (ref "J10") (pin "b10") (pinfunction "b10_b10") (pintype "bidirectional"))
    )
    (net (code "176") (name "/RTM_FPGA_DONE") (class "Default")
      (node (ref "J10") (pin "a9") (pinfunction "a9_a9") (pintype "bidirectional"))
    )
    (net (code "177") (name "/RTM_FPGA_INIT_B") (class "Default")
      (node (ref "J10") (pin "b8") (pinfunction "b8_b8") (pintype "bidirectional"))
    )
    (net (code "178") (name "/RTM_FPGA_PROGRAM_B") (class "Default")
      (node (ref "J10") (pin "b9") (pinfunction "b9_b9") (pintype "bidirectional"))
    )
    (net (code "179") (name "/RTM_PSn") (class "Default")
      (node (ref "J11") (pin "c1") (pinfunction "c1_c1") (pintype "bidirectional"))
    )
    (net (code "180") (name "/RTM_SCL") (class "Default")
      (node (ref "J11") (pin "d2") (pinfunction "d2_d2") (pintype "bidirectional"))
    )
    (net (code "181") (name "/RTM_SDA") (class "Default")
      (node (ref "J11") (pin "d1") (pinfunction "d1_d1") (pintype "bidirectional"))
    )
    (net (code "182") (name "/RTM_TCK") (class "Default")
      (node (ref "J11") (pin "e1") (pinfunction "e1_e1") (pintype "bidirectional"))
    )
    (net (code "183") (name "/RTM_TDI") (class "Default")
      (node (ref "J11") (pin "e2") (pinfunction "e2_e2") (pintype "bidirectional"))
    )
    (net (code "184") (name "/RTM_TDO") (class "Default")
      (node (ref "J11") (pin "f1") (pinfunction "f1_f1") (pintype "bidirectional"))
    )
    (net (code "185") (name "/RTM_TMS") (class "Default")
      (node (ref "J11") (pin "f2") (pinfunction "f2_f2") (pintype "bidirectional"))
    )
    (net (code "186") (name "/RTM_UART_Rx") (class "Default")
      (node (ref "J10") (pin "b7") (pinfunction "b7_b7") (pintype "bidirectional"))
    )
    (net (code "187") (name "/RTM_UART_Tx") (class "Default")
      (node (ref "J10") (pin "a7") (pinfunction "a7_a7") (pintype "bidirectional"))
    )
    (net (code "196") (name "GND") (class "Default")
      (node (ref "J10") (pin "bG1") (pinfunction "bG1_bG1") (pintype "power_in"))
      (node (ref "J10") (pin "bG10") (pinfunction "bG10_bG10") (pintype "power_in"))
      (node (ref "J10") (pin "bG2") (pinfunction "bG2_bG2") (pintype "power_in"))
      (node (ref "J10") (pin "bG3") (pinfunction "bG3_bG3") (pintype "power_in"))
      (node (ref "J10") (pin "bG4") (pinfunction "bG4_bG4") (pintype "power_in"))
      (node (ref "J10") (pin "bG5") (pinfunction "bG5_bG5") (pintype "power_in"))
      (node (ref "J10") (pin "bG6") (pinfunction "bG6_bG6") (pintype "power_in"))
      (node (ref "J10") (pin "bG7") (pinfunction "bG7_bG7") (pintype "power_in"))
      (node (ref "J10") (pin "bG8") (pinfunction "bG8_bG8") (pintype "power_in"))
      (node (ref "J10") (pin "bG9") (pinfunction "bG9_bG9") (pintype "power_in"))
      (node (ref "J10") (pin "dG1") (pinfunction "dG1_dG1") (pintype "power_in"))
      (node (ref "J10") (pin "dG10") (pinfunction "dG10_dG10") (pintype "power_in"))
      (node (ref "J10") (pin "dG2") (pinfunction "dG2_dG2") (pintype "power_in"))
      (node (ref "J10") (pin "dG3") (pinfunction "dG3_dG3") (pintype "power_in"))
      (node (ref "J10") (pin "dG4") (pinfunction "dG4_dG4") (pintype "power_in"))
      (node (ref "J10") (pin "dG5") (pinfunction "dG5_dG5") (pintype "power_in"))
      (node (ref "J10") (pin "dG6") (pinfunction "dG6_dG6") (pintype "power_in"))
      (node (ref "J10") (pin "dG7") (pinfunction "dG7_dG7") (pintype "power_in"))
      (node (ref "J10") (pin "dG8") (pinfunction "dG8_dG8") (pintype "power_in"))
      (node (ref "J10") (pin "dG9") (pinfunction "dG9_dG9") (pintype "power_in"))
      (node (ref "J10") (pin "fG1") (pinfunction "fG1_fG1") (pintype "power_in"))
      (node (ref "J10") (pin "fG10") (pinfunction "fG10_fG10") (pintype "power_in"))
      (node (ref "J10") (pin "fG2") (pinfunction "fG2_fG2") (pintype "power_in"))
      (node (ref "J10") (pin "fG3") (pinfunction "fG3_fG3") (pintype "power_in"))
      (node (ref "J10") (pin "fG4") (pinfunction "fG4_fG4") (pintype "power_in"))
      (node (ref "J10") (pin "fG5") (pinfunction "fG5_fG5") (pintype "power_in"))
      (node (ref "J10") (pin "fG6") (pinfunction "fG6_fG6") (pintype "power_in"))
      (node (ref "J10") (pin "fG7") (pinfunction "fG7_fG7") (pintype "power_in"))
      (node (ref "J10") (pin "fG8") (pinfunction "fG8_fG8") (pintype "power_in"))
      (node (ref "J10") (pin "fG9") (pinfunction "fG9_fG9") (pintype "power_in"))
      (node (ref "J11") (pin "bG1") (pinfunction "bG1_bG1") (pintype "power_in"))
      (node (ref "J11") (pin "bG10") (pinfunction "bG10_bG10") (pintype "power_in"))
      (node (ref "J11") (pin "bG2") (pinfunction "bG2_bG2") (pintype "power_in"))
      (node (ref "J11") (pin "bG3") (pinfunction "bG3_bG3") (pintype "power_in"))
      (node (ref "J11") (pin "bG4") (pinfunction "bG4_bG4") (pintype "power_in"))
      (node (ref "J11") (pin "bG5") (pinfunction "bG5_bG5") (pintype "power_in"))
      (node (ref "J11") (pin "bG6") (pinfunction "bG6_bG6") (pintype "power_in"))
      (node (ref "J11") (pin "bG7") (pinfunction "bG7_bG7") (pintype "power_in"))
      (node (ref "J11") (pin "bG8") (pinfunction "bG8_bG8") (pintype "power_in"))
      (node (ref "J11") (pin "bG9") (pinfunction "bG9_bG9") (pintype "power_in"))
      (node (ref "J11") (pin "dG1") (pinfunction "dG1_dG1") (pintype "power_in"))
      (node (ref "J11") (pin "dG10") (pinfunction "dG10_dG10") (pintype "power_in"))
      (node (ref "J11") (pin "dG2") (pinfunction "dG2_dG2") (pintype "power_in"))
      (node (ref "J11") (pin "dG3") (pinfunction "dG3_dG3") (pintype "power_in"))
      (node (ref "J11") (pin "dG4") (pinfunction "dG4_dG4") (pintype "power_in"))
      (node (ref "J11") (pin "dG5") (pinfunction "dG5_dG5") (pintype "power_in"))
      (node (ref "J11") (pin "dG6") (pinfunction "dG6_dG6") (pintype "power_in"))
      (node (ref "J11") (pin "dG7") (pinfunction "dG7_dG7") (pintype "power_in"))
      (node (ref "J11") (pin "dG8") (pinfunction "dG8_dG8") (pintype "power_in"))
      (node (ref "J11") (pin "dG9") (pinfunction "dG9_dG9") (pintype "power_in"))
      (node (ref "J11") (pin "fG1") (pinfunction "fG1_fG1") (pintype "power_in"))
      (node (ref "J11") (pin "fG10") (pinfunction "fG10_fG10") (pintype "power_in"))
      (node (ref "J11") (pin "fG2") (pinfunction "fG2_fG2") (pintype "power_in"))
      (node (ref "J11") (pin "fG3") (pinfunction "fG3_fG3") (pintype "power_in"))
      (node (ref "J11") (pin "fG4") (pinfunction "fG4_fG4") (pintype "power_in"))
      (node (ref "J11") (pin "fG5") (pinfunction "fG5_fG5") (pintype "power_in"))
      (node (ref "J11") (pin "fG6") (pinfunction "fG6_fG6") (pintype "power_in"))
      (node (ref "J11") (pin "fG7") (pinfunction "fG7_fG7") (pintype "power_in"))
      (node (ref "J11") (pin "fG8") (pinfunction "fG8_fG8") (pintype "power_in"))
      (node (ref "J11") (pin "fG9") (pinfunction "fG9_fG9") (pintype "power_in"))
      (node (ref "R12") (pin "1") (pinfunction "1_1") (pintype "passive"))
    )
    (net (code "197") (name "P3V3MP_RTM") (class "Default")
      (node (ref "J11") (pin "c2") (pinfunction "c2_c2") (pintype "bidirectional"))
    )
    (net (code "198") (name "P12V0_RTM") (class "Default")
      (node (ref "J11") (pin "a1") (pinfunction "a1_a1") (pintype "bidirectional"))
      (node (ref "J11") (pin "a2") (pinfunction "a2_a2") (pintype "bidirectional"))
      (node (ref "J11") (pin "b1") (pinfunction "b1_b1") (pintype "bidirectional"))
      (node (ref "J11") (pin "b2") (pinfunction "b2_b2") (pintype "bidirectional"))
    )
    (net (code "199") (name "unconnected-(J10-Pada8)") (class "Default")
      (node (ref "J10") (pin "a8") (pinfunction "a8_a8") (pintype "bidirectional"))
    )
  )
)
